# SMD_RGB_COM_AO3402_REV1.net
KiCad netlist of a schematic drawn in EAGLE
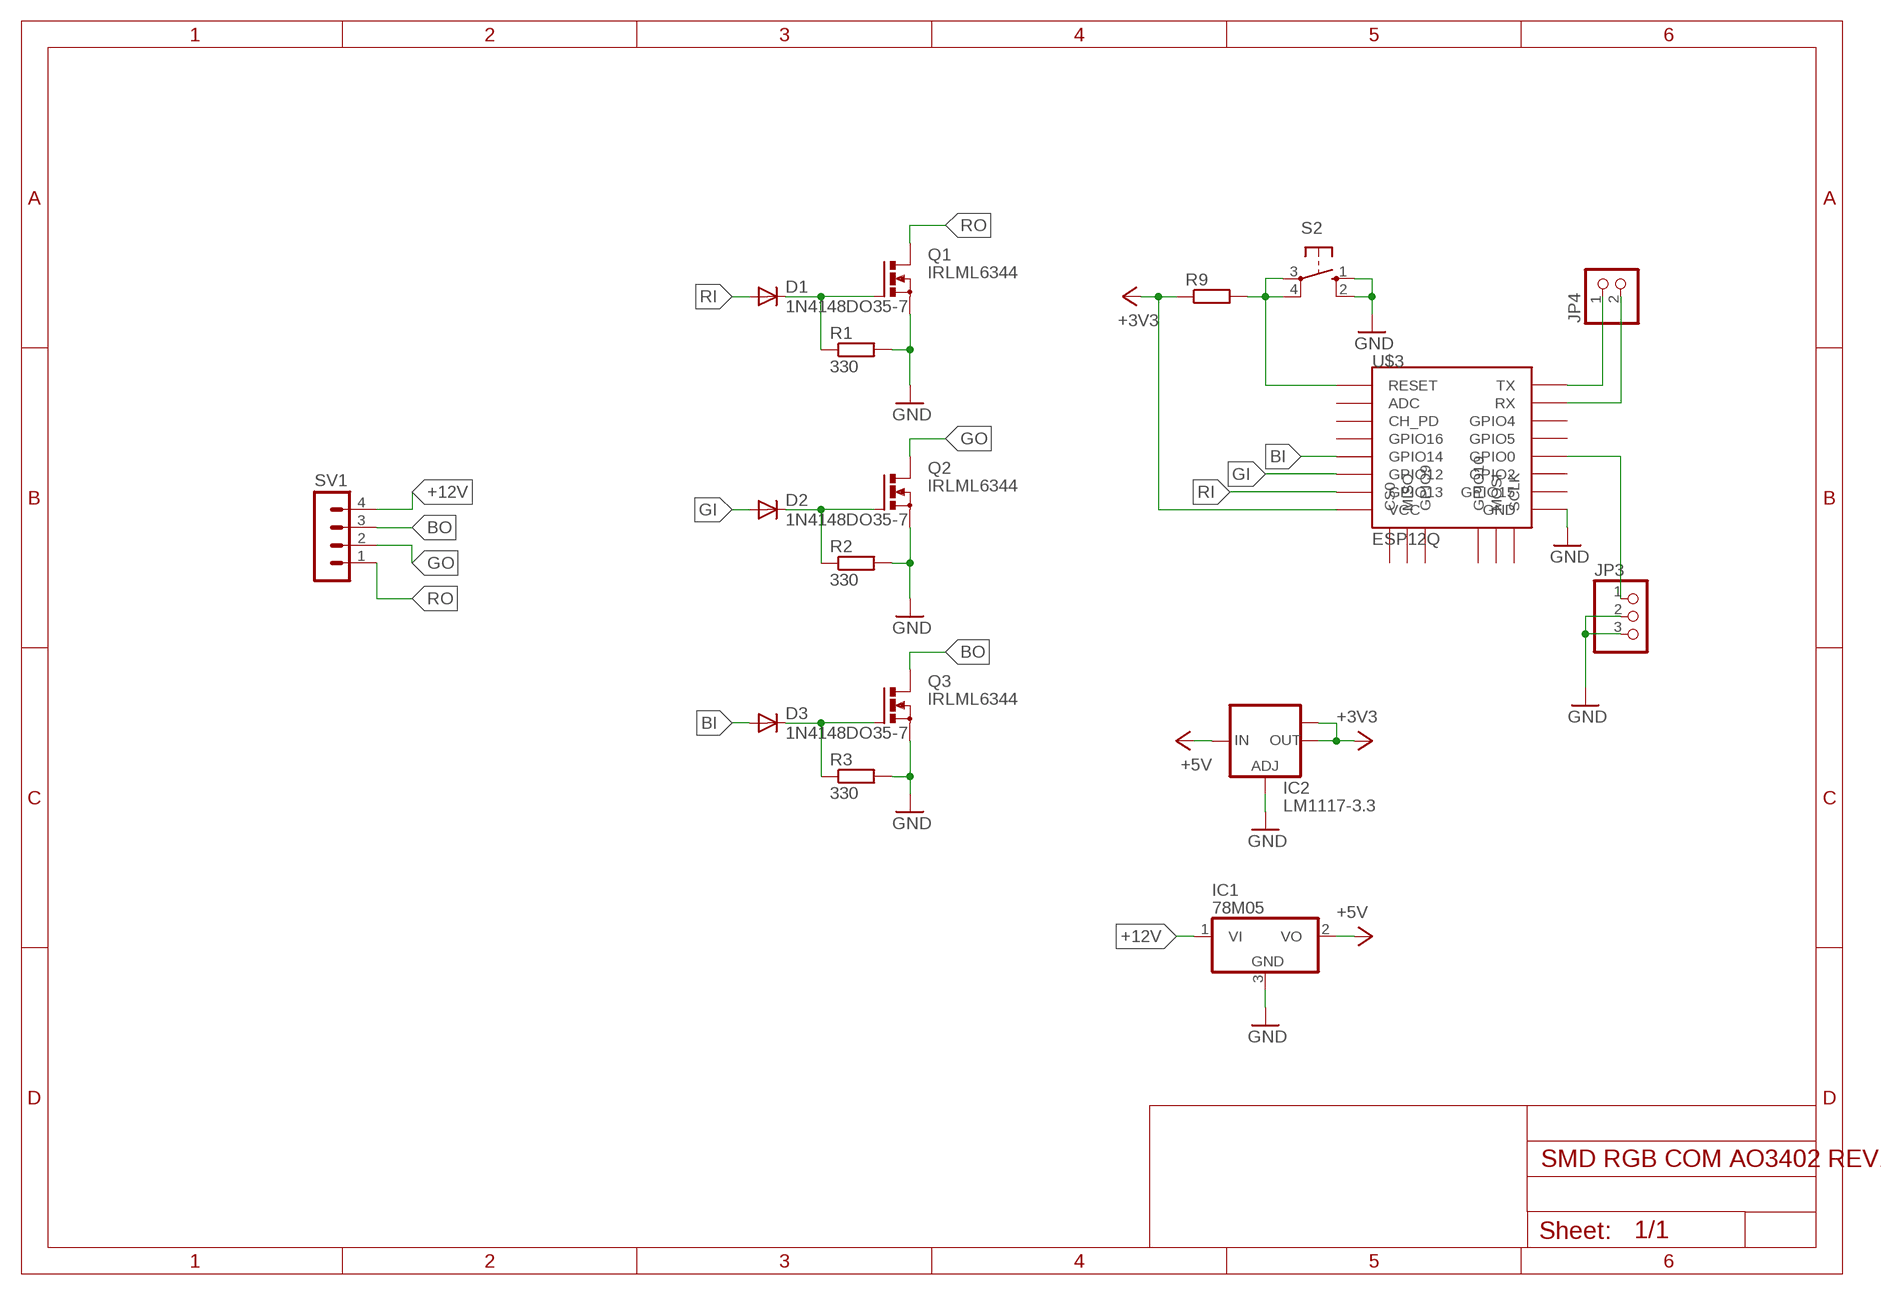
[diagram p0: schematic, sheet 1]

(export (version "E")
  (design (tool "Eeschema 10.0.6"))
  (components
    (comp (ref "D1")
      (value "1N4148DO35-7")
      (footprint "eagle-import:DO35-7")
      (libsource (lib "eagle-import") (part "1N4148DO35-7"))
    )
    (comp (ref "D2")
      (value "1N4148DO35-7")
      (footprint "eagle-import:DO35-7")
      (libsource (lib "eagle-import") (part "1N4148DO35-7"))
    )
    (comp (ref "D3")
      (value "1N4148DO35-7")
      (footprint "eagle-import:DO35-7")
      (libsource (lib "eagle-import") (part "1N4148DO35-7"))
    )
    (comp (ref "IC1")
      (value "78M05")
      (footprint "eagle-import:TO252")
      (libsource (lib "eagle-import") (part "78DT05"))
    )
    (comp (ref "IC2")
      (value "LM1117-3.3")
      (footprint "eagle-import:SOT223")
      (libsource (lib "eagle-import") (part "LM1117IMPX-ADJ"))
    )
    (comp (ref "JP3")
      (value "PINHD-1X3")
      (footprint "eagle-import:1X03")
      (libsource (lib "eagle-import") (part "PINHD-1X3"))
    )
    (comp (ref "JP4")
      (value "PINHD-1X2")
      (footprint "eagle-import:1X02")
      (libsource (lib "eagle-import") (part "PINHD-1X2"))
    )
    (comp (ref "Q1")
      (value "IRLML6344")
      (footprint "eagle-import:SOT-23")
      (libsource (lib "eagle-import") (part "IRLML6344"))
    )
    (comp (ref "Q2")
      (value "IRLML6344")
      (footprint "eagle-import:SOT-23")
      (libsource (lib "eagle-import") (part "IRLML6344"))
    )
    (comp (ref "Q3")
      (value "IRLML6344")
      (footprint "eagle-import:SOT-23")
      (libsource (lib "eagle-import") (part "IRLML6344"))
    )
    (comp (ref "R1")
      (value "330")
      (footprint "eagle-import:0204_7")
      (libsource (lib "eagle-import") (part "R-EU_0204/7"))
    )
    (comp (ref "R2")
      (value "330")
      (footprint "eagle-import:0204_7")
      (libsource (lib "eagle-import") (part "rcl_334_R-EU_0204/7"))
    )
    (comp (ref "R3")
      (value "330")
      (footprint "eagle-import:0204_7")
      (libsource (lib "eagle-import") (part "R-EU_0204/7"))
    )
    (comp (ref "R9")
      (value "R-EU_0204/7")
      (footprint "eagle-import:0204_7")
      (libsource (lib "eagle-import") (part "rcl_334_R-EU_0204/7"))
    )
    (comp (ref "S2")
      (value "10-XX")
      (footprint "eagle-import:B3F-10XX")
      (fields (field (name "MPN") "B3F-1000"))
      (libsource (lib "eagle-import") (part "10-XX"))
    )
    (comp (ref "SV1")
      (value "MA04-1")
      (footprint "eagle-import:MA04-1")
      (libsource (lib "eagle-import") (part "MA04-1"))
    )
    (comp (ref "U$3")
      (value "ESP12Q")
      (footprint "eagle-import:ESP12Q")
      (libsource (lib "eagle-import") (part "ESP12Q"))
    )
  )
  (nets
    (net (code "1") (name "+3V3") (class "Default")
      (node (ref "IC2") (pin "2") (pinfunction "OUT_2") (pintype "passive"))
      (node (ref "IC2") (pin "TAB") (pinfunction "OUT1_TAB") (pintype "passive"))
      (node (ref "R9") (pin "1") (pinfunction "1_1") (pintype "passive"))
      (node (ref "U$3") (pin "VCC") (pinfunction "VCC_VCC") (pintype "bidirectional"))
    )
    (net (code "2") (name "+5V") (class "Default")
      (node (ref "IC1") (pin "2") (pinfunction "VO_2") (pintype "passive"))
      (node (ref "IC2") (pin "3") (pinfunction "IN_3") (pintype "input"))
    )
    (net (code "3") (name "+12V") (class "Default")
      (node (ref "IC1") (pin "1") (pinfunction "VI_1") (pintype "input"))
      (node (ref "SV1") (pin "4") (pinfunction "4_4") (pintype "passive"))
    )
    (net (code "4") (name "BI") (class "Default")
      (node (ref "D3") (pin "A") (pinfunction "A_A") (pintype "passive"))
      (node (ref "U$3") (pin "GPIO14") (pinfunction "GPIO14_GPIO14") (pintype "bidirectional"))
    )
    (net (code "5") (name "BO") (class "Default")
      (node (ref "Q3") (pin "P3") (pinfunction "D_P3") (pintype "passive"))
      (node (ref "SV1") (pin "3") (pinfunction "3_3") (pintype "passive"))
    )
    (net (code "6") (name "GI") (class "Default")
      (node (ref "D2") (pin "A") (pinfunction "A_A") (pintype "passive"))
      (node (ref "U$3") (pin "GPIO12") (pinfunction "GPIO12_GPIO12") (pintype "bidirectional"))
    )
    (net (code "7") (name "GND") (class "Default")
      (node (ref "IC1") (pin "3") (pinfunction "GND_3") (pintype "passive"))
      (node (ref "IC2") (pin "1") (pinfunction "ADJ_1") (pintype "input"))
      (node (ref "JP3") (pin "2") (pinfunction "2_2") (pintype "passive"))
      (node (ref "JP3") (pin "3") (pinfunction "3_3") (pintype "passive"))
      (node (ref "Q1") (pin "P2") (pinfunction "S_P2") (pintype "passive"))
      (node (ref "Q2") (pin "P2") (pinfunction "S_P2") (pintype "passive"))
      (node (ref "Q3") (pin "P2") (pinfunction "S_P2") (pintype "passive"))
      (node (ref "R1") (pin "2") (pinfunction "2_2") (pintype "passive"))
      (node (ref "R2") (pin "2") (pinfunction "2_2") (pintype "passive"))
      (node (ref "R3") (pin "2") (pinfunction "2_2") (pintype "passive"))
      (node (ref "S2") (pin "1") (pinfunction "S_1") (pintype "passive"))
      (node (ref "S2") (pin "2") (pinfunction "S1_2") (pintype "passive"))
      (node (ref "U$3") (pin "GND") (pinfunction "GND_GND") (pintype "bidirectional"))
    )
    (net (code "8") (name "GO") (class "Default")
      (node (ref "Q2") (pin "P3") (pinfunction "D_P3") (pintype "passive"))
      (node (ref "SV1") (pin "2") (pinfunction "2_2") (pintype "passive"))
    )
    (net (code "9") (name "Net-(JP3-Pad1)") (class "Default")
      (node (ref "JP3") (pin "1") (pinfunction "1_1") (pintype "passive"))
      (node (ref "U$3") (pin "GPIO0") (pinfunction "GPIO0_GPIO0") (pintype "bidirectional"))
    )
    (net (code "10") (name "Net-(JP4-Pad1)") (class "Default")
      (node (ref "JP4") (pin "1") (pinfunction "1_1") (pintype "passive"))
      (node (ref "U$3") (pin "TX") (pinfunction "TX_TX") (pintype "bidirectional"))
    )
    (net (code "11") (name "Net-(JP4-Pad2)") (class "Default")
      (node (ref "JP4") (pin "2") (pinfunction "2_2") (pintype "passive"))
      (node (ref "U$3") (pin "RX") (pinfunction "RX_RX") (pintype "bidirectional"))
    )
    (net (code "12") (name "Net-(Q1-G)") (class "Default")
      (node (ref "D1") (pin "C") (pinfunction "C_C") (pintype "passive"))
      (node (ref "Q1") (pin "P1") (pinfunction "G_P1") (pintype "passive"))
      (node (ref "R1") (pin "1") (pinfunction "1_1") (pintype "passive"))
    )
    (net (code "13") (name "Net-(Q2-G)") (class "Default")
      (node (ref "D2") (pin "C") (pinfunction "C_C") (pintype "passive"))
      (node (ref "Q2") (pin "P1") (pinfunction "G_P1") (pintype "passive"))
      (node (ref "R2") (pin "1") (pinfunction "1_1") (pintype "passive"))
    )
    (net (code "14") (name "Net-(Q3-G)") (class "Default")
      (node (ref "D3") (pin "C") (pinfunction "C_C") (pintype "passive"))
      (node (ref "Q3") (pin "P1") (pinfunction "G_P1") (pintype "passive"))
      (node (ref "R3") (pin "1") (pinfunction "1_1") (pintype "passive"))
    )
    (net (code "15") (name "Net-(S2-P)") (class "Default")
      (node (ref "R9") (pin "2") (pinfunction "2_2") (pintype "passive"))
      (node (ref "S2") (pin "3") (pinfunction "P_3") (pintype "passive"))
      (node (ref "S2") (pin "4") (pinfunction "P1_4") (pintype "passive"))
      (node (ref "U$3") (pin "RESET") (pinfunction "RESET_RESET") (pintype "bidirectional"))
    )
    (net (code "16") (name "RI") (class "Default")
      (node (ref "D1") (pin "A") (pinfunction "A_A") (pintype "passive"))
      (node (ref "U$3") (pin "GPIO13") (pinfunction "GPIO13_GPIO13") (pintype "bidirectional"))
    )
    (net (code "17") (name "RO") (class "Default")
      (node (ref "Q1") (pin "P3") (pinfunction "D_P3") (pintype "passive"))
      (node (ref "SV1") (pin "1") (pinfunction "1_1") (pintype "passive"))
    )
    (net (code "18") (name "unconnected-(U$3-PadADC)") (class "Default")
      (node (ref "U$3") (pin "ADC") (pinfunction "ADC_ADC") (pintype "bidirectional"))
    )
    (net (code "19") (name "unconnected-(U$3-PadCH_PD)") (class "Default")
      (node (ref "U$3") (pin "CH_PD") (pinfunction "CH_PD_CH_PD") (pintype "bidirectional"))
    )
    (net (code "20") (name "unconnected-(U$3-PadCS0)") (class "Default")
      (node (ref "U$3") (pin "CS0") (pinfunction "CS0_CS0") (pintype "bidirectional"))
    )
    (net (code "21") (name "unconnected-(U$3-PadGPIO2)") (class "Default")
      (node (ref "U$3") (pin "GPIO2") (pinfunction "GPIO2_GPIO2") (pintype "bidirectional"))
    )
    (net (code "22") (name "unconnected-(U$3-PadGPIO4)") (class "Default")
      (node (ref "U$3") (pin "GPIO4") (pinfunction "GPIO4_GPIO4") (pintype "bidirectional"))
    )
    (net (code "23") (name "unconnected-(U$3-PadGPIO5)") (class "Default")
      (node (ref "U$3") (pin "GPIO5") (pinfunction "GPIO5_GPIO5") (pintype "bidirectional"))
    )
    (net (code "24") (name "unconnected-(U$3-PadGPIO9)") (class "Default")
      (node (ref "U$3") (pin "GPIO9") (pinfunction "GPIO9_GPIO9") (pintype "bidirectional"))
    )
    (net (code "25") (name "unconnected-(U$3-PadGPIO10)") (class "Default")
      (node (ref "U$3") (pin "GPIO10") (pinfunction "GPIO10_GPIO10") (pintype "bidirectional"))
    )
    (net (code "26") (name "unconnected-(U$3-PadGPIO15)") (class "Default")
      (node (ref "U$3") (pin "GPIO15") (pinfunction "GPIO15_GPIO15") (pintype "bidirectional"))
    )
    (net (code "27") (name "unconnected-(U$3-PadGPIO16)") (class "Default")
      (node (ref "U$3") (pin "GPIO16") (pinfunction "GPIO16_GPIO16") (pintype "bidirectional"))
    )
    (net (code "28") (name "unconnected-(U$3-PadMISO)") (class "Default")
      (node (ref "U$3") (pin "MISO") (pinfunction "MISO_MISO") (pintype "bidirectional"))
    )
    (net (code "29") (name "unconnected-(U$3-PadMOSI)") (class "Default")
      (node (ref "U$3") (pin "MOSI") (pinfunction "MOSI_MOSI") (pintype "bidirectional"))
    )
    (net (code "30") (name "unconnected-(U$3-PadSCLK)") (class "Default")
      (node (ref "U$3") (pin "SCLK") (pinfunction "SCLK_SCLK") (pintype "bidirectional"))
    )
  )
)
